# cube8.net
KiCad netlist of a schematic drawn in Altium Designer
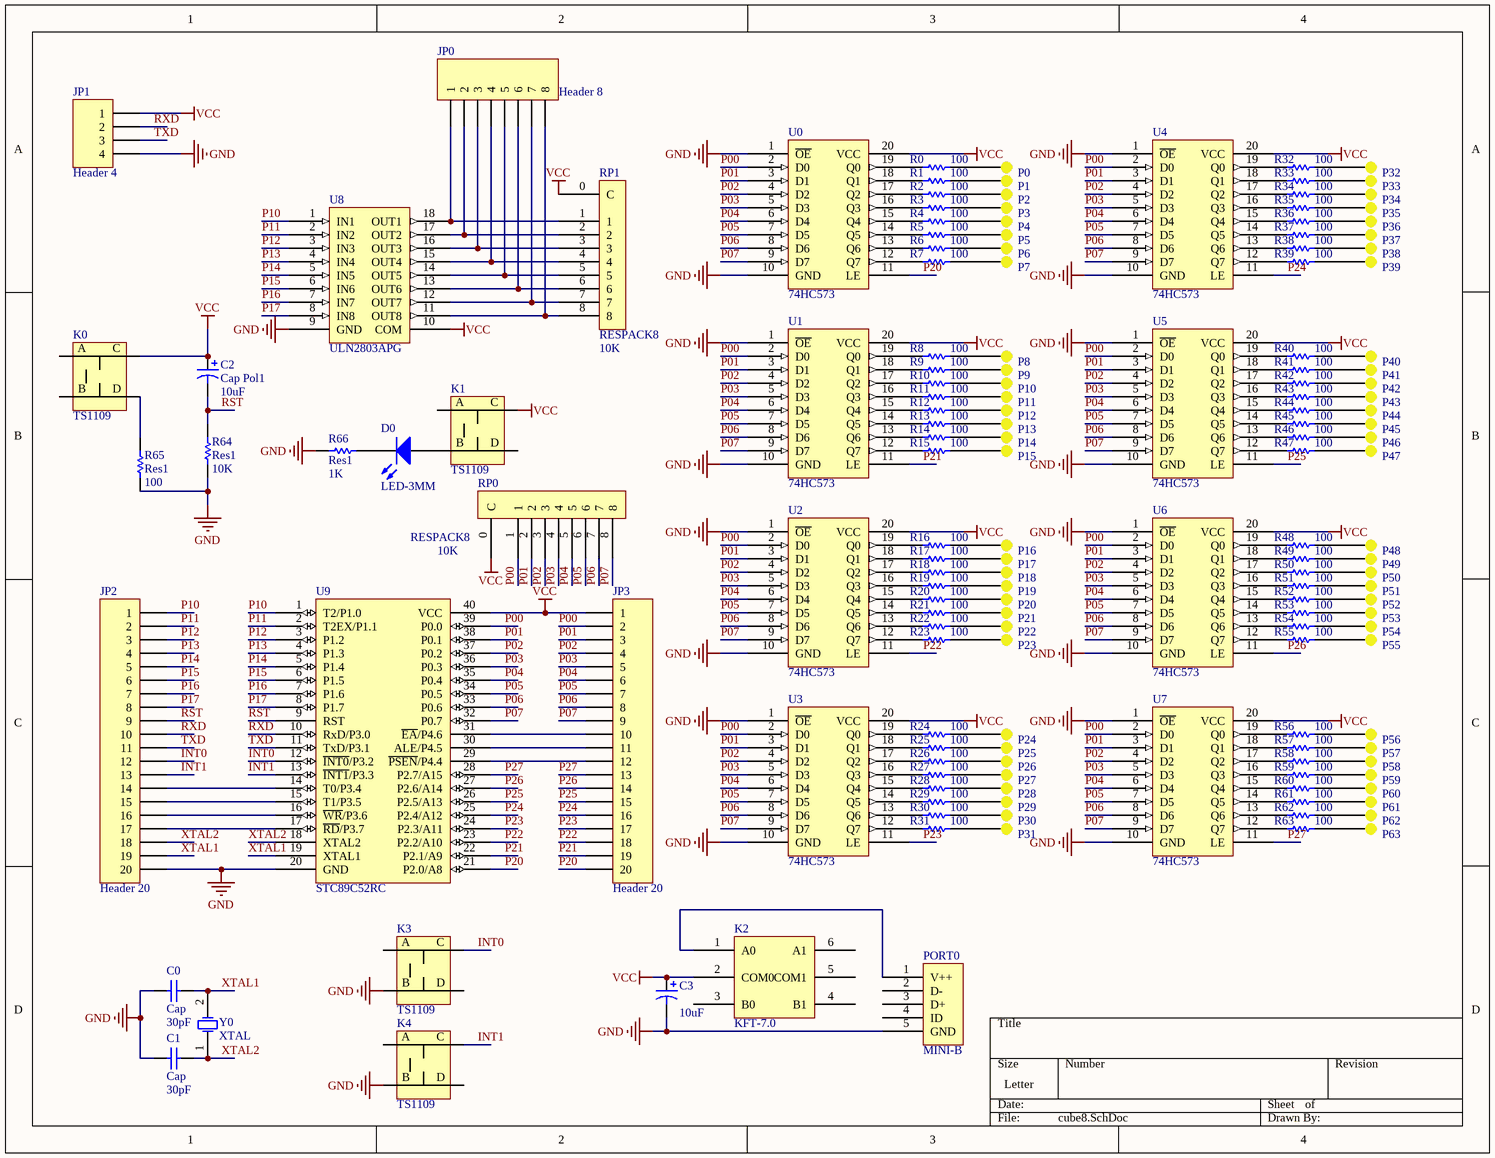
[diagram p0: cube8.SchDoc]

(export (version "E")
  (design (tool "Eeschema 10.0.6"))
  (components
    (comp (ref "C0")
      (value "Cap")
      (footprint "RAD-0.1")
      (description "Capacitor")
      (fields (field (name "ALTIUM_VALUE") "30pF") (field (name "PUBLISHER") "Altium Limited"))
      (libsource (lib "Miscellaneous Devices") (part "Cap"))
    )
    (comp (ref "C1")
      (value "Cap")
      (footprint "RAD-0.1")
      (description "Capacitor")
      (fields (field (name "ALTIUM_VALUE") "30pF") (field (name "PUBLISHER") "Altium Limited"))
      (libsource (lib "Miscellaneous Devices") (part "Cap"))
    )
    (comp (ref "C2")
      (value "Cap Pol1")
      (footprint "RB.1")
      (description "Polarized Capacitor (Radial)")
      (fields (field (name "ALTIUM_VALUE") "10uF") (field (name "PUBLISHER") "Altium Limited"))
      (libsource (lib "Miscellaneous Devices") (part "Cap Pol1"))
    )
    (comp (ref "C3")
      (value "10uF")
      (footprint "RB.1")
      (description "Polarized Capacitor (Radial)")
      (fields (field (name "Comment") "Cap Pol1") (field (name "PUBLISHER") "Altium Limited"))
      (libsource (lib "Miscellaneous Devices") (part "Cap Pol1"))
    )
    (comp (ref "D0")
      (value "LED-3MM")
      (footprint "LED3")
      (description "Typical INFRARED GaAs LED")
      (fields (field (name "PUBLISHER") "Altium Limited"))
      (libsource (lib "Miscellaneous Devices") (part "LED0"))
    )
    (comp (ref "JP0")
      (value "Header 8")
      (footprint "HDR1X8")
      (description "Header, 8-Pin")
      (fields (field (name "PUBLISHER") "Altium Limited"))
      (libsource (lib "Miscellaneous Connectors") (part "Header 8"))
    )
    (comp (ref "JP1")
      (value "Header 4")
      (footprint "PIN4")
      (description "Header, 4-Pin")
      (fields (field (name "PUBLISHER") "Altium Limited"))
      (libsource (lib "Miscellaneous Connectors") (part "Header 4"))
    )
    (comp (ref "JP2")
      (value "Header 20")
      (footprint "HDR1X20")
      (description "Header, 20-Pin")
      (fields (field (name "PUBLISHER") "Altium Limited"))
      (libsource (lib "") (part "Header 20_1"))
    )
    (comp (ref "JP3")
      (value "Header 20")
      (footprint "HDR1X20")
      (description "Header, 20-Pin")
      (fields (field (name "PUBLISHER") "Altium Limited"))
      (libsource (lib "Miscellaneous Connectors") (part "Header 20"))
    )
    (comp (ref "K0") (value "TS1109") (footprint "TS-1109") (libsource (lib "cube8") (part "TS-1109")))
    (comp (ref "K1") (value "TS1109") (footprint "TS-1109") (libsource (lib "cube8") (part "TS-1109")))
    (comp (ref "K2") (value "KFT-7.0") (footprint "KFT-7.0") (libsource (lib "cube8") (part "KFT-7.0")))
    (comp (ref "K3") (value "TS1109") (footprint "TS-1109") (libsource (lib "cube8") (part "TS-1109")))
    (comp (ref "K4") (value "TS1109") (footprint "TS-1109") (libsource (lib "cube8") (part "TS-1109")))
    (comp (ref "P0") (value "PIN") (footprint "PIN1") (libsource (lib "cube8") (part "PIN1")))
    (comp (ref "P1") (value "PIN") (footprint "PIN1") (libsource (lib "cube8") (part "PIN1")))
    (comp (ref "P2") (value "PIN") (footprint "PIN1") (libsource (lib "cube8") (part "PIN1")))
    (comp (ref "P3") (value "PIN") (footprint "PIN1") (libsource (lib "cube8") (part "PIN1")))
    (comp (ref "P4") (value "PIN") (footprint "PIN1") (libsource (lib "cube8") (part "PIN1")))
    (comp (ref "P5") (value "PIN") (footprint "PIN1") (libsource (lib "cube8") (part "PIN1")))
    (comp (ref "P6") (value "PIN") (footprint "PIN1") (libsource (lib "cube8") (part "PIN1")))
    (comp (ref "P7") (value "PIN") (footprint "PIN1") (libsource (lib "cube8") (part "PIN1")))
    (comp (ref "P8") (value "PIN") (footprint "PIN1") (libsource (lib "cube8") (part "PIN1")))
    (comp (ref "P9") (value "PIN") (footprint "PIN1") (libsource (lib "cube8") (part "PIN1")))
    (comp (ref "P10") (value "PIN") (footprint "PIN1") (libsource (lib "cube8") (part "PIN1")))
    (comp (ref "P11") (value "PIN") (footprint "PIN1") (libsource (lib "cube8") (part "PIN1")))
    (comp (ref "P12") (value "PIN") (footprint "PIN1") (libsource (lib "cube8") (part "PIN1")))
    (comp (ref "P13") (value "PIN") (footprint "PIN1") (libsource (lib "cube8") (part "PIN1")))
    (comp (ref "P14") (value "PIN") (footprint "PIN1") (libsource (lib "cube8") (part "PIN1")))
    (comp (ref "P15") (value "PIN") (footprint "PIN1") (libsource (lib "cube8") (part "PIN1")))
    (comp (ref "P16") (value "PIN") (footprint "PIN1") (libsource (lib "cube8") (part "PIN1")))
    (comp (ref "P17") (value "PIN") (footprint "PIN1") (libsource (lib "cube8") (part "PIN1")))
    (comp (ref "P18") (value "PIN") (footprint "PIN1") (libsource (lib "cube8") (part "PIN1")))
    (comp (ref "P19") (value "PIN") (footprint "PIN1") (libsource (lib "cube8") (part "PIN1")))
    (comp (ref "P20") (value "PIN") (footprint "PIN1") (libsource (lib "cube8") (part "PIN1")))
    (comp (ref "P21") (value "PIN") (footprint "PIN1") (libsource (lib "cube8") (part "PIN1")))
    (comp (ref "P22") (value "PIN") (footprint "PIN1") (libsource (lib "cube8") (part "PIN1")))
    (comp (ref "P23") (value "PIN") (footprint "PIN1") (libsource (lib "cube8") (part "PIN1")))
    (comp (ref "P24") (value "PIN") (footprint "PIN1") (libsource (lib "cube8") (part "PIN1")))
    (comp (ref "P25") (value "PIN") (footprint "PIN1") (libsource (lib "cube8") (part "PIN1")))
    (comp (ref "P26") (value "PIN") (footprint "PIN1") (libsource (lib "cube8") (part "PIN1")))
    (comp (ref "P27") (value "PIN") (footprint "PIN1") (libsource (lib "cube8") (part "PIN1")))
    (comp (ref "P28") (value "PIN") (footprint "PIN1") (libsource (lib "cube8") (part "PIN1")))
    (comp (ref "P29") (value "PIN") (footprint "PIN1") (libsource (lib "cube8") (part "PIN1")))
    (comp (ref "P30") (value "PIN") (footprint "PIN1") (libsource (lib "cube8") (part "PIN1")))
    (comp (ref "P31") (value "PIN") (footprint "PIN1") (libsource (lib "cube8") (part "PIN1")))
    (comp (ref "P32") (value "PIN") (footprint "PIN1") (libsource (lib "cube8") (part "PIN1")))
    (comp (ref "P33") (value "PIN") (footprint "PIN1") (libsource (lib "cube8") (part "PIN1")))
    (comp (ref "P34") (value "PIN") (footprint "PIN1") (libsource (lib "cube8") (part "PIN1")))
    (comp (ref "P35") (value "PIN") (footprint "PIN1") (libsource (lib "cube8") (part "PIN1")))
    (comp (ref "P36") (value "PIN") (footprint "PIN1") (libsource (lib "cube8") (part "PIN1")))
    (comp (ref "P37") (value "PIN") (footprint "PIN1") (libsource (lib "cube8") (part "PIN1")))
    (comp (ref "P38") (value "PIN") (footprint "PIN1") (libsource (lib "cube8") (part "PIN1")))
    (comp (ref "P39") (value "PIN") (footprint "PIN1") (libsource (lib "cube8") (part "PIN1")))
    (comp (ref "P40") (value "PIN") (footprint "PIN1") (libsource (lib "cube8") (part "PIN1")))
    (comp (ref "P41") (value "PIN") (footprint "PIN1") (libsource (lib "cube8") (part "PIN1")))
    (comp (ref "P42") (value "PIN") (footprint "PIN1") (libsource (lib "cube8") (part "PIN1")))
    (comp (ref "P43") (value "PIN") (footprint "PIN1") (libsource (lib "cube8") (part "PIN1")))
    (comp (ref "P44") (value "PIN") (footprint "PIN1") (libsource (lib "cube8") (part "PIN1")))
    (comp (ref "P45") (value "PIN") (footprint "PIN1") (libsource (lib "cube8") (part "PIN1")))
    (comp (ref "P46") (value "PIN") (footprint "PIN1") (libsource (lib "cube8") (part "PIN1")))
    (comp (ref "P47") (value "PIN") (footprint "PIN1") (libsource (lib "cube8") (part "PIN1")))
    (comp (ref "P48") (value "PIN") (footprint "PIN1") (libsource (lib "cube8") (part "PIN1")))
    (comp (ref "P49") (value "PIN") (footprint "PIN1") (libsource (lib "cube8") (part "PIN1")))
    (comp (ref "P50") (value "PIN") (footprint "PIN1") (libsource (lib "cube8") (part "PIN1")))
    (comp (ref "P51") (value "PIN") (footprint "PIN1") (libsource (lib "cube8") (part "PIN1")))
    (comp (ref "P52") (value "PIN") (footprint "PIN1") (libsource (lib "cube8") (part "PIN1")))
    (comp (ref "P53") (value "PIN") (footprint "PIN1") (libsource (lib "cube8") (part "PIN1")))
    (comp (ref "P54") (value "PIN") (footprint "PIN1") (libsource (lib "cube8") (part "PIN1")))
    (comp (ref "P55") (value "PIN") (footprint "PIN1") (libsource (lib "cube8") (part "PIN1")))
    (comp (ref "P56") (value "PIN") (footprint "PIN1") (libsource (lib "cube8") (part "PIN1")))
    (comp (ref "P57") (value "PIN") (footprint "PIN1") (libsource (lib "cube8") (part "PIN1")))
    (comp (ref "P58") (value "PIN") (footprint "PIN1") (libsource (lib "cube8") (part "PIN1")))
    (comp (ref "P59") (value "PIN") (footprint "PIN1") (libsource (lib "cube8") (part "PIN1")))
    (comp (ref "P60") (value "PIN") (footprint "PIN1") (libsource (lib "cube8") (part "PIN1")))
    (comp (ref "P61") (value "PIN") (footprint "PIN1") (libsource (lib "cube8") (part "PIN1")))
    (comp (ref "P62") (value "PIN") (footprint "PIN1") (libsource (lib "cube8") (part "PIN1")))
    (comp (ref "P63") (value "PIN") (footprint "PIN1") (libsource (lib "cube8") (part "PIN1")))
    (comp (ref "PORT0") (value "MINI-B") (footprint "MINI-B") (libsource (lib "cube8") (part "MINI-B")))
    (comp (ref "R0")
      (value "100")
      (footprint "AXIAL-0.3")
      (description "Resistor")
      (fields (field (name "Comment") "Res1") (field (name "PUBLISHER") "Altium Limited"))
      (libsource (lib "Miscellaneous Devices") (part "Res1"))
    )
    (comp (ref "R1")
      (value "100")
      (footprint "AXIAL-0.3")
      (description "Resistor")
      (fields (field (name "Comment") "Res1") (field (name "PUBLISHER") "Altium Limited"))
      (libsource (lib "Miscellaneous Devices") (part "Res1"))
    )
    (comp (ref "R2")
      (value "100")
      (footprint "AXIAL-0.3")
      (description "Resistor")
      (fields (field (name "Comment") "Res1") (field (name "PUBLISHER") "Altium Limited"))
      (libsource (lib "Miscellaneous Devices") (part "Res1"))
    )
    (comp (ref "R3")
      (value "100")
      (footprint "AXIAL-0.3")
      (description "Resistor")
      (fields (field (name "Comment") "Res1") (field (name "PUBLISHER") "Altium Limited"))
      (libsource (lib "Miscellaneous Devices") (part "Res1"))
    )
    (comp (ref "R4")
      (value "100")
      (footprint "AXIAL-0.3")
      (description "Resistor")
      (fields (field (name "Comment") "Res1") (field (name "PUBLISHER") "Altium Limited"))
      (libsource (lib "Miscellaneous Devices") (part "Res1"))
    )
    (comp (ref "R5")
      (value "100")
      (footprint "AXIAL-0.3")
      (description "Resistor")
      (fields (field (name "Comment") "Res1") (field (name "PUBLISHER") "Altium Limited"))
      (libsource (lib "Miscellaneous Devices") (part "Res1"))
    )
    (comp (ref "R6")
      (value "100")
      (footprint "AXIAL-0.3")
      (description "Resistor")
      (fields (field (name "Comment") "Res1") (field (name "PUBLISHER") "Altium Limited"))
      (libsource (lib "Miscellaneous Devices") (part "Res1"))
    )
    (comp (ref "R7")
      (value "100")
      (footprint "AXIAL-0.3")
      (description "Resistor")
      (fields (field (name "Comment") "Res1") (field (name "PUBLISHER") "Altium Limited"))
      (libsource (lib "Miscellaneous Devices") (part "Res1"))
    )
    (comp (ref "R8")
      (value "100")
      (footprint "AXIAL-0.3")
      (description "Resistor")
      (fields (field (name "Comment") "Res1") (field (name "PUBLISHER") "Altium Limited"))
      (libsource (lib "Miscellaneous Devices") (part "Res1"))
    )
    (comp (ref "R9")
      (value "100")
      (footprint "AXIAL-0.3")
      (description "Resistor")
      (fields (field (name "Comment") "Res1") (field (name "PUBLISHER") "Altium Limited"))
      (libsource (lib "Miscellaneous Devices") (part "Res1"))
    )
    (comp (ref "R10")
      (value "100")
      (footprint "AXIAL-0.3")
      (description "Resistor")
      (fields (field (name "Comment") "Res1") (field (name "PUBLISHER") "Altium Limited"))
      (libsource (lib "Miscellaneous Devices") (part "Res1"))
    )
    (comp (ref "R11")
      (value "100")
      (footprint "AXIAL-0.3")
      (description "Resistor")
      (fields (field (name "Comment") "Res1") (field (name "PUBLISHER") "Altium Limited"))
      (libsource (lib "Miscellaneous Devices") (part "Res1"))
    )
    (comp (ref "R12")
      (value "100")
      (footprint "AXIAL-0.3")
      (description "Resistor")
      (fields (field (name "Comment") "Res1") (field (name "PUBLISHER") "Altium Limited"))
      (libsource (lib "Miscellaneous Devices") (part "Res1"))
    )
    (comp (ref "R13")
      (value "100")
      (footprint "AXIAL-0.3")
      (description "Resistor")
      (fields (field (name "Comment") "Res1") (field (name "PUBLISHER") "Altium Limited"))
      (libsource (lib "Miscellaneous Devices") (part "Res1"))
    )
    (comp (ref "R14")
      (value "100")
      (footprint "AXIAL-0.3")
      (description "Resistor")
      (fields (field (name "Comment") "Res1") (field (name "PUBLISHER") "Altium Limited"))
      (libsource (lib "Miscellaneous Devices") (part "Res1"))
    )
    (comp (ref "R15")
      (value "100")
      (footprint "AXIAL-0.3")
      (description "Resistor")
      (fields (field (name "Comment") "Res1") (field (name "PUBLISHER") "Altium Limited"))
      (libsource (lib "Miscellaneous Devices") (part "Res1"))
    )
    (comp (ref "R16")
      (value "100")
      (footprint "AXIAL-0.3")
      (description "Resistor")
      (fields (field (name "Comment") "Res1") (field (name "PUBLISHER") "Altium Limited"))
      (libsource (lib "Miscellaneous Devices") (part "Res1"))
    )
    (comp (ref "R17")
      (value "100")
      (footprint "AXIAL-0.3")
      (description "Resistor")
      (fields (field (name "Comment") "Res1") (field (name "PUBLISHER") "Altium Limited"))
      (libsource (lib "Miscellaneous Devices") (part "Res1"))
    )
    (comp (ref "R18")
      (value "100")
      (footprint "AXIAL-0.3")
      (description "Resistor")
      (fields (field (name "Comment") "Res1") (field (name "PUBLISHER") "Altium Limited"))
      (libsource (lib "Miscellaneous Devices") (part "Res1"))
    )
    (comp (ref "R19")
      (value "100")
      (footprint "AXIAL-0.3")
      (description "Resistor")
      (fields (field (name "Comment") "Res1") (field (name "PUBLISHER") "Altium Limited"))
      (libsource (lib "Miscellaneous Devices") (part "Res1"))
    )
    (comp (ref "R20")
      (value "100")
      (footprint "AXIAL-0.3")
      (description "Resistor")
      (fields (field (name "Comment") "Res1") (field (name "PUBLISHER") "Altium Limited"))
      (libsource (lib "Miscellaneous Devices") (part "Res1"))
    )
    (comp (ref "R21")
      (value "100")
      (footprint "AXIAL-0.3")
      (description "Resistor")
      (fields (field (name "Comment") "Res1") (field (name "PUBLISHER") "Altium Limited"))
      (libsource (lib "Miscellaneous Devices") (part "Res1"))
    )
    (comp (ref "R22")
      (value "100")
      (footprint "AXIAL-0.3")
      (description "Resistor")
      (fields (field (name "Comment") "Res1") (field (name "PUBLISHER") "Altium Limited"))
      (libsource (lib "Miscellaneous Devices") (part "Res1"))
    )
    (comp (ref "R23")
      (value "100")
      (footprint "AXIAL-0.3")
      (description "Resistor")
      (fields (field (name "Comment") "Res1") (field (name "PUBLISHER") "Altium Limited"))
      (libsource (lib "Miscellaneous Devices") (part "Res1"))
    )
    (comp (ref "R24")
      (value "100")
      (footprint "AXIAL-0.3")
      (description "Resistor")
      (fields (field (name "Comment") "Res1") (field (name "PUBLISHER") "Altium Limited"))
      (libsource (lib "Miscellaneous Devices") (part "Res1"))
    )
    (comp (ref "R25")
      (value "100")
      (footprint "AXIAL-0.3")
      (description "Resistor")
      (fields (field (name "Comment") "Res1") (field (name "PUBLISHER") "Altium Limited"))
      (libsource (lib "Miscellaneous Devices") (part "Res1"))
    )
    (comp (ref "R26")
      (value "100")
      (footprint "AXIAL-0.3")
      (description "Resistor")
      (fields (field (name "Comment") "Res1") (field (name "PUBLISHER") "Altium Limited"))
      (libsource (lib "Miscellaneous Devices") (part "Res1"))
    )
    (comp (ref "R27")
      (value "100")
      (footprint "AXIAL-0.3")
      (description "Resistor")
      (fields (field (name "Comment") "Res1") (field (name "PUBLISHER") "Altium Limited"))
      (libsource (lib "Miscellaneous Devices") (part "Res1"))
    )
    (comp (ref "R28")
      (value "100")
      (footprint "AXIAL-0.3")
      (description "Resistor")
      (fields (field (name "Comment") "Res1") (field (name "PUBLISHER") "Altium Limited"))
      (libsource (lib "Miscellaneous Devices") (part "Res1"))
    )
    (comp (ref "R29")
      (value "100")
      (footprint "AXIAL-0.3")
      (description "Resistor")
      (fields (field (name "Comment") "Res1") (field (name "PUBLISHER") "Altium Limited"))
      (libsource (lib "Miscellaneous Devices") (part "Res1"))
    )
    (comp (ref "R30")
      (value "100")
      (footprint "AXIAL-0.3")
      (description "Resistor")
      (fields (field (name "Comment") "Res1") (field (name "PUBLISHER") "Altium Limited"))
      (libsource (lib "Miscellaneous Devices") (part "Res1"))
    )
    (comp (ref "R31")
      (value "100")
      (footprint "AXIAL-0.3")
      (description "Resistor")
      (fields (field (name "Comment") "Res1") (field (name "PUBLISHER") "Altium Limited"))
      (libsource (lib "Miscellaneous Devices") (part "Res1"))
    )
    (comp (ref "R32")
      (value "100")
      (footprint "AXIAL-0.3")
      (description "Resistor")
      (fields (field (name "Comment") "Res1") (field (name "PUBLISHER") "Altium Limited"))
      (libsource (lib "Miscellaneous Devices") (part "Res1"))
    )
    (comp (ref "R33")
      (value "100")
      (footprint "AXIAL-0.3")
      (description "Resistor")
      (fields (field (name "Comment") "Res1") (field (name "PUBLISHER") "Altium Limited"))
      (libsource (lib "Miscellaneous Devices") (part "Res1"))
    )
    (comp (ref "R34")
      (value "100")
      (footprint "AXIAL-0.3")
      (description "Resistor")
      (fields (field (name "Comment") "Res1") (field (name "PUBLISHER") "Altium Limited"))
      (libsource (lib "Miscellaneous Devices") (part "Res1"))
    )
    (comp (ref "R35")
      (value "100")
      (footprint "AXIAL-0.3")
      (description "Resistor")
      (fields (field (name "Comment") "Res1") (field (name "PUBLISHER") "Altium Limited"))
      (libsource (lib "Miscellaneous Devices") (part "Res1"))
    )
    (comp (ref "R36")
      (value "100")
      (footprint "AXIAL-0.3")
      (description "Resistor")
      (fields (field (name "Comment") "Res1") (field (name "PUBLISHER") "Altium Limited"))
      (libsource (lib "Miscellaneous Devices") (part "Res1"))
    )
    (comp (ref "R37")
      (value "100")
      (footprint "AXIAL-0.3")
      (description "Resistor")
      (fields (field (name "Comment") "Res1") (field (name "PUBLISHER") "Altium Limited"))
      (libsource (lib "Miscellaneous Devices") (part "Res1"))
    )
    (comp (ref "R38")
      (value "100")
      (footprint "AXIAL-0.3")
      (description "Resistor")
      (fields (field (name "Comment") "Res1") (field (name "PUBLISHER") "Altium Limited"))
      (libsource (lib "Miscellaneous Devices") (part "Res1"))
    )
    (comp (ref "R39")
      (value "100")
      (footprint "AXIAL-0.3")
      (description "Resistor")
      (fields (field (name "Comment") "Res1") (field (name "PUBLISHER") "Altium Limited"))
      (libsource (lib "Miscellaneous Devices") (part "Res1"))
    )
    (comp (ref "R40")
      (value "100")
      (footprint "AXIAL-0.3")
      (description "Resistor")
      (fields (field (name "Comment") "Res1") (field (name "PUBLISHER") "Altium Limited"))
      (libsource (lib "Miscellaneous Devices") (part "Res1"))
    )
    (comp (ref "R41")
      (value "100")
      (footprint "AXIAL-0.3")
      (description "Resistor")
      (fields (field (name "Comment") "Res1") (field (name "PUBLISHER") "Altium Limited"))
      (libsource (lib "Miscellaneous Devices") (part "Res1"))
    )
    (comp (ref "R42")
      (value "100")
      (footprint "AXIAL-0.3")
      (description "Resistor")
      (fields (field (name "Comment") "Res1") (field (name "PUBLISHER") "Altium Limited"))
      (libsource (lib "Miscellaneous Devices") (part "Res1"))
    )
    (comp (ref "R43")
      (value "100")
      (footprint "AXIAL-0.3")
      (description "Resistor")
      (fields (field (name "Comment") "Res1") (field (name "PUBLISHER") "Altium Limited"))
      (libsource (lib "Miscellaneous Devices") (part "Res1"))
    )
    (comp (ref "R44")
      (value "100")
      (footprint "AXIAL-0.3")
      (description "Resistor")
      (fields (field (name "Comment") "Res1") (field (name "PUBLISHER") "Altium Limited"))
      (libsource (lib "Miscellaneous Devices") (part "Res1"))
    )
    (comp (ref "R45")
      (value "100")
      (footprint "AXIAL-0.3")
      (description "Resistor")
      (fields (field (name "Comment") "Res1") (field (name "PUBLISHER") "Altium Limited"))
      (libsource (lib "Miscellaneous Devices") (part "Res1"))
    )
    (comp (ref "R46")
      (value "100")
      (footprint "AXIAL-0.3")
      (description "Resistor")
      (fields (field (name "Comment") "Res1") (field (name "PUBLISHER") "Altium Limited"))
      (libsource (lib "Miscellaneous Devices") (part "Res1"))
    )
    (comp (ref "R47")
      (value "100")
      (footprint "AXIAL-0.3")
      (description "Resistor")
      (fields (field (name "Comment") "Res1") (field (name "PUBLISHER") "Altium Limited"))
      (libsource (lib "Miscellaneous Devices") (part "Res1"))
    )
    (comp (ref "R48")
      (value "100")
      (footprint "AXIAL-0.3")
      (description "Resistor")
      (fields (field (name "Comment") "Res1") (field (name "PUBLISHER") "Altium Limited"))
      (libsource (lib "Miscellaneous Devices") (part "Res1"))
    )
    (comp (ref "R49")
      (value "100")
      (footprint "AXIAL-0.3")
      (description "Resistor")
      (fields (field (name "Comment") "Res1") (field (name "PUBLISHER") "Altium Limited"))
      (libsource (lib "Miscellaneous Devices") (part "Res1"))
    )
    (comp (ref "R50")
      (value "100")
      (footprint "AXIAL-0.3")
      (description "Resistor")
      (fields (field (name "Comment") "Res1") (field (name "PUBLISHER") "Altium Limited"))
      (libsource (lib "Miscellaneous Devices") (part "Res1"))
    )
    (comp (ref "R51")
      (value "100")
      (footprint "AXIAL-0.3")
      (description "Resistor")
      (fields (field (name "Comment") "Res1") (field (name "PUBLISHER") "Altium Limited"))
      (libsource (lib "Miscellaneous Devices") (part "Res1"))
    )
    (comp (ref "R52")
      (value "100")
      (footprint "AXIAL-0.3")
      (description "Resistor")
      (fields (field (name "Comment") "Res1") (field (name "PUBLISHER") "Altium Limited"))
      (libsource (lib "Miscellaneous Devices") (part "Res1"))
    )
    (comp (ref "R53")
      (value "100")
      (footprint "AXIAL-0.3")
      (description "Resistor")
      (fields (field (name "Comment") "Res1") (field (name "PUBLISHER") "Altium Limited"))
      (libsource (lib "Miscellaneous Devices") (part "Res1"))
    )
    (comp (ref "R54")
      (value "100")
      (footprint "AXIAL-0.3")
      (description "Resistor")
      (fields (field (name "Comment") "Res1") (field (name "PUBLISHER") "Altium Limited"))
      (libsource (lib "Miscellaneous Devices") (part "Res1"))
    )
    (comp (ref "R55")
      (value "100")
      (footprint "AXIAL-0.3")
      (description "Resistor")
      (fields (field (name "Comment") "Res1") (field (name "PUBLISHER") "Altium Limited"))
      (libsource (lib "Miscellaneous Devices") (part "Res1"))
    )
    (comp (ref "R56")
      (value "100")
      (footprint "AXIAL-0.3")
      (description "Resistor")
      (fields (field (name "Comment") "Res1") (field (name "PUBLISHER") "Altium Limited"))
      (libsource (lib "Miscellaneous Devices") (part "Res1"))
    )
    (comp (ref "R57")
      (value "100")
      (footprint "AXIAL-0.3")
      (description "Resistor")
      (fields (field (name "Comment") "Res1") (field (name "PUBLISHER") "Altium Limited"))
      (libsource (lib "Miscellaneous Devices") (part "Res1"))
    )
    (comp (ref "R58")
      (value "100")
      (footprint "AXIAL-0.3")
      (description "Resistor")
      (fields (field (name "Comment") "Res1") (field (name "PUBLISHER") "Altium Limited"))
      (libsource (lib "Miscellaneous Devices") (part "Res1"))
    )
    (comp (ref "R59")
      (value "100")
      (footprint "AXIAL-0.3")
      (description "Resistor")
      (fields (field (name "Comment") "Res1") (field (name "PUBLISHER") "Altium Limited"))
      (libsource (lib "Miscellaneous Devices") (part "Res1"))
    )
    (comp (ref "R60")
      (value "100")
      (footprint "AXIAL-0.3")
      (description "Resistor")
      (fields (field (name "Comment") "Res1") (field (name "PUBLISHER") "Altium Limited"))
      (libsource (lib "Miscellaneous Devices") (part "Res1"))
    )
    (comp (ref "R61")
      (value "100")
      (footprint "AXIAL-0.3")
      (description "Resistor")
      (fields (field (name "Comment") "Res1") (field (name "PUBLISHER") "Altium Limited"))
      (libsource (lib "Miscellaneous Devices") (part "Res1"))
    )
    (comp (ref "R62")
      (value "100")
      (footprint "AXIAL-0.3")
      (description "Resistor")
      (fields (field (name "Comment") "Res1") (field (name "PUBLISHER") "Altium Limited"))
      (libsource (lib "Miscellaneous Devices") (part "Res1"))
    )
    (comp (ref "R63")
      (value "100")
      (footprint "AXIAL-0.3")
      (description "Resistor")
      (fields (field (name "Comment") "Res1") (field (name "PUBLISHER") "Altium Limited"))
      (libsource (lib "Miscellaneous Devices") (part "Res1"))
    )
    (comp (ref "R64")
      (value "Res1")
      (footprint "AXIAL-0.3")
      (description "Resistor")
      (fields (field (name "ALTIUM_VALUE") "10K") (field (name "PUBLISHER") "Altium Limited"))
      (libsource (lib "Miscellaneous Devices") (part "Res1"))
    )
    (comp (ref "R65")
      (value "Res1")
      (footprint "AXIAL-0.3")
      (description "Resistor")
      (fields (field (name "ALTIUM_VALUE") "100") (field (name "PUBLISHER") "Altium Limited"))
      (libsource (lib "Miscellaneous Devices") (part "Res1"))
    )
    (comp (ref "R66")
      (value "Res1")
      (footprint "AXIAL-0.3")
      (description "Resistor")
      (fields (field (name "ALTIUM_VALUE") "1K") (field (name "PUBLISHER") "Altium Limited"))
      (libsource (lib "Miscellaneous Devices") (part "Res1"))
    )
    (comp (ref "RP0")
      (value "RESPACK8")
      (footprint "SIP9")
      (fields (field (name "ALTIUM_VALUE") "10K"))
      (libsource (lib "cube8") (part "RESPACK8"))
    )
    (comp (ref "RP1")
      (value "RESPACK8")
      (footprint "SIP9")
      (fields (field (name "ALTIUM_VALUE") "10K"))
      (libsource (lib "") (part "RESPACK8_1"))
    )
    (comp (ref "U0") (value "74HC573") (footprint "DIP20") (libsource (lib "cube8") (part "74HC573")))
    (comp (ref "U1") (value "74HC573") (footprint "DIP20") (libsource (lib "cube8") (part "74HC573")))
    (comp (ref "U2") (value "74HC573") (footprint "DIP20") (libsource (lib "cube8") (part "74HC573")))
    (comp (ref "U3") (value "74HC573") (footprint "DIP20") (libsource (lib "cube8") (part "74HC573")))
    (comp (ref "U4") (value "74HC573") (footprint "DIP20") (libsource (lib "cube8") (part "74HC573")))
    (comp (ref "U5") (value "74HC573") (footprint "DIP20") (libsource (lib "cube8") (part "74HC573")))
    (comp (ref "U6") (value "74HC573") (footprint "DIP20") (libsource (lib "cube8") (part "74HC573")))
    (comp (ref "U7") (value "74HC573") (footprint "DIP20") (libsource (lib "cube8") (part "74HC573")))
    (comp (ref "U8") (value "ULN2803APG") (footprint "DIP18") (libsource (lib "cube8") (part "ULN2803APG")))
    (comp (ref "U9") (value "STC89C52RC") (footprint "DIP40") (libsource (lib "cube8") (part "STC89C52RC")))
    (comp (ref "Y0")
      (value "XTAL")
      (footprint "HC-49S")
      (description "Crystal Oscillator")
      (fields (field (name "PUBLISHER") "Altium Limited"))
      (libsource (lib "Miscellaneous Devices") (part "XTAL"))
    )
  )
  (nets
    (net (code "1") (name "/INT0") (class "Default")
      (node (ref "JP2") (pin "12") (pinfunction "12_12") (pintype "passive"))
      (node (ref "K3") (pin "C") (pinfunction "12_C") (pintype "passive"))
      (node (ref "U9") (pin "12") (pinfunction "~{INT0}/P3.2_12") (pintype "bidirectional"))
    )
    (net (code "2") (name "/INT1") (class "Default")
      (node (ref "JP2") (pin "13") (pinfunction "13_13") (pintype "passive"))
      (node (ref "K4") (pin "C") (pinfunction "12_C") (pintype "passive"))
      (node (ref "U9") (pin "13") (pinfunction "~{INT1}/P3.3_13") (pintype "bidirectional"))
    )
    (net (code "3") (name "/P00") (class "Default")
      (node (ref "JP3") (pin "2") (pinfunction "2_2") (pintype "passive"))
      (node (ref "RP0") (pin "1") (pinfunction "1_1") (pintype "passive"))
      (node (ref "U0") (pin "2") (pinfunction "D0_2") (pintype "input"))
      (node (ref "U1") (pin "2") (pinfunction "D0_2") (pintype "input"))
      (node (ref "U2") (pin "2") (pinfunction "D0_2") (pintype "input"))
      (node (ref "U3") (pin "2") (pinfunction "D0_2") (pintype "input"))
      (node (ref "U4") (pin "2") (pinfunction "D0_2") (pintype "input"))
      (node (ref "U5") (pin "2") (pinfunction "D0_2") (pintype "input"))
      (node (ref "U6") (pin "2") (pinfunction "D0_2") (pintype "input"))
      (node (ref "U7") (pin "2") (pinfunction "D0_2") (pintype "input"))
      (node (ref "U9") (pin "39") (pinfunction "P0.0_39") (pintype "bidirectional"))
    )
    (net (code "4") (name "/P01") (class "Default")
      (node (ref "JP3") (pin "3") (pinfunction "3_3") (pintype "passive"))
      (node (ref "RP0") (pin "2") (pinfunction "2_2") (pintype "passive"))
      (node (ref "U0") (pin "3") (pinfunction "D1_3") (pintype "input"))
      (node (ref "U1") (pin "3") (pinfunction "D1_3") (pintype "input"))
      (node (ref "U2") (pin "3") (pinfunction "D1_3") (pintype "input"))
      (node (ref "U3") (pin "3") (pinfunction "D1_3") (pintype "input"))
      (node (ref "U4") (pin "3") (pinfunction "D1_3") (pintype "input"))
      (node (ref "U5") (pin "3") (pinfunction "D1_3") (pintype "input"))
      (node (ref "U6") (pin "3") (pinfunction "D1_3") (pintype "input"))
      (node (ref "U7") (pin "3") (pinfunction "D1_3") (pintype "input"))
      (node (ref "U9") (pin "38") (pinfunction "P0.1_38") (pintype "bidirectional"))
    )
    (net (code "5") (name "/P02") (class "Default")
      (node (ref "JP3") (pin "4") (pinfunction "4_4") (pintype "passive"))
      (node (ref "RP0") (pin "3") (pinfunction "3_3") (pintype "passive"))
      (node (ref "U0") (pin "4") (pinfunction "D2_4") (pintype "input"))
      (node (ref "U1") (pin "4") (pinfunction "D2_4") (pintype "input"))
      (node (ref "U2") (pin "4") (pinfunction "D2_4") (pintype "input"))
      (node (ref "U3") (pin "4") (pinfunction "D2_4") (pintype "input"))
      (node (ref "U4") (pin "4") (pinfunction "D2_4") (pintype "input"))
      (node (ref "U5") (pin "4") (pinfunction "D2_4") (pintype "input"))
      (node (ref "U6") (pin "4") (pinfunction "D2_4") (pintype "input"))
      (node (ref "U7") (pin "4") (pinfunction "D2_4") (pintype "input"))
      (node (ref "U9") (pin "37") (pinfunction "P0.2_37") (pintype "bidirectional"))
    )
    (net (code "6") (name "/P03") (class "Default")
      (node (ref "JP3") (pin "5") (pinfunction "5_5") (pintype "passive"))
      (node (ref "RP0") (pin "4") (pinfunction "4_4") (pintype "passive"))
      (node (ref "U0") (pin "5") (pinfunction "D3_5") (pintype "input"))
      (node (ref "U1") (pin "5") (pinfunction "D3_5") (pintype "input"))
      (node (ref "U2") (pin "5") (pinfunction "D3_5") (pintype "input"))
      (node (ref "U3") (pin "5") (pinfunction "D3_5") (pintype "input"))
      (node (ref "U4") (pin "5") (pinfunction "D3_5") (pintype "input"))
      (node (ref "U5") (pin "5") (pinfunction "D3_5") (pintype "input"))
      (node (ref "U6") (pin "5") (pinfunction "D3_5") (pintype "input"))
      (node (ref "U7") (pin "5") (pinfunction "D3_5") (pintype "input"))
      (node (ref "U9") (pin "36") (pinfunction "P0.3_36") (pintype "bidirectional"))
    )
    (net (code "7") (name "/P04") (class "Default")
      (node (ref "JP3") (pin "6") (pinfunction "6_6") (pintype "passive"))
      (node (ref "RP0") (pin "5") (pinfunction "5_5") (pintype "passive"))
      (node (ref "U0") (pin "6") (pinfunction "D4_6") (pintype "input"))
      (node (ref "U1") (pin "6") (pinfunction "D4_6") (pintype "input"))
      (node (ref "U2") (pin "6") (pinfunction "D4_6") (pintype "input"))
      (node (ref "U3") (pin "6") (pinfunction "D4_6") (pintype "input"))
      (node (ref "U4") (pin "6") (pinfunction "D4_6") (pintype "input"))
      (node (ref "U5") (pin "6") (pinfunction "D4_6") (pintype "input"))
      (node (ref "U6") (pin "6") (pinfunction "D4_6") (pintype "input"))
      (node (ref "U7") (pin "6") (pinfunction "D4_6") (pintype "input"))
      (node (ref "U9") (pin "35") (pinfunction "P0.4_35") (pintype "bidirectional"))
    )
    (net (code "8") (name "/P05") (class "Default")
      (node (ref "JP3") (pin "7") (pinfunction "7_7") (pintype "passive"))
      (node (ref "RP0") (pin "6") (pinfunction "6_6") (pintype "passive"))
      (node (ref "U0") (pin "7") (pinfunction "D5_7") (pintype "input"))
      (node (ref "U1") (pin "7") (pinfunction "D5_7") (pintype "input"))
      (node (ref "U2") (pin "7") (pinfunction "D5_7") (pintype "input"))
      (node (ref "U3") (pin "7") (pinfunction "D5_7") (pintype "input"))
      (node (ref "U4") (pin "7") (pinfunction "D5_7") (pintype "input"))
      (node (ref "U5") (pin "7") (pinfunction "D5_7") (pintype "input"))
      (node (ref "U6") (pin "7") (pinfunction "D5_7") (pintype "input"))
      (node (ref "U7") (pin "7") (pinfunction "D5_7") (pintype "input"))
      (node (ref "U9") (pin "34") (pinfunction "P0.5_34") (pintype "bidirectional"))
    )
    (net (code "9") (name "/P06") (class "Default")
      (node (ref "JP3") (pin "8") (pinfunction "8_8") (pintype "passive"))
      (node (ref "RP0") (pin "7") (pinfunction "7_7") (pintype "passive"))
      (node (ref "U0") (pin "8") (pinfunction "D6_8") (pintype "input"))
      (node (ref "U1") (pin "8") (pinfunction "D6_8") (pintype "input"))
      (node (ref "U2") (pin "8") (pinfunction "D6_8") (pintype "input"))
      (node (ref "U3") (pin "8") (pinfunction "D6_8") (pintype "input"))
      (node (ref "U4") (pin "8") (pinfunction "D6_8") (pintype "input"))
      (node (ref "U5") (pin "8") (pinfunction "D6_8") (pintype "input"))
      (node (ref "U6") (pin "8") (pinfunction "D6_8") (pintype "input"))
      (node (ref "U7") (pin "8") (pinfunction "D6_8") (pintype "input"))
      (node (ref "U9") (pin "33") (pinfunction "P0.6_33") (pintype "bidirectional"))
    )
    (net (code "10") (name "/P07") (class "Default")
      (node (ref "JP3") (pin "9") (pinfunction "9_9") (pintype "passive"))
      (node (ref "RP0") (pin "8") (pinfunction "8_8") (pintype "passive"))
      (node (ref "U0") (pin "9") (pinfunction "D7_9") (pintype "input"))
      (node (ref "U1") (pin "9") (pinfunction "D7_9") (pintype "input"))
      (node (ref "U2") (pin "9") (pinfunction "D7_9") (pintype "input"))
      (node (ref "U3") (pin "9") (pinfunction "D7_9") (pintype "input"))
      (node (ref "U4") (pin "9") (pinfunction "D7_9") (pintype "input"))
      (node (ref "U5") (pin "9") (pinfunction "D7_9") (pintype "input"))
      (node (ref "U6") (pin "9") (pinfunction "D7_9") (pintype "input"))
      (node (ref "U7") (pin "9") (pinfunction "D7_9") (pintype "input"))
      (node (ref "U9") (pin "32") (pinfunction "P0.7_32") (pintype "bidirectional"))
    )
    (net (code "11") (name "/P10") (class "Default")
      (node (ref "JP2") (pin "1") (pinfunction "1_1") (pintype "passive"))
      (node (ref "U8") (pin "1") (pinfunction "IN1_1") (pintype "input"))
      (node (ref "U9") (pin "1") (pinfunction "T2/P1.0_1") (pintype "bidirectional"))
    )
    (net (code "12") (name "/P11") (class "Default")
      (node (ref "JP2") (pin "2") (pinfunction "2_2") (pintype "passive"))
      (node (ref "U8") (pin "2") (pinfunction "IN2_2") (pintype "input"))
      (node (ref "U9") (pin "2") (pinfunction "T2EX/P1.1_2") (pintype "bidirectional"))
    )
    (net (code "13") (name "/P12") (class "Default")
      (node (ref "JP2") (pin "3") (pinfunction "3_3") (pintype "passive"))
      (node (ref "U8") (pin "3") (pinfunction "IN3_3") (pintype "input"))
      (node (ref "U9") (pin "3") (pinfunction "P1.2_3") (pintype "bidirectional"))
    )
    (net (code "14") (name "/P13") (class "Default")
      (node (ref "JP2") (pin "4") (pinfunction "4_4") (pintype "passive"))
      (node (ref "U8") (pin "4") (pinfunction "IN4_4") (pintype "input"))
      (node (ref "U9") (pin "4") (pinfunction "P1.3_4") (pintype "bidirectional"))
    )
    (net (code "15") (name "/P14") (class "Default")
      (node (ref "JP2") (pin "5") (pinfunction "5_5") (pintype "passive"))
      (node (ref "U8") (pin "5") (pinfunction "IN5_5") (pintype "input"))
      (node (ref "U9") (pin "5") (pinfunction "P1.4_5") (pintype "bidirectional"))
    )
    (net (code "16") (name "/P15") (class "Default")
      (node (ref "JP2") (pin "6") (pinfunction "6_6") (pintype "passive"))
      (node (ref "U8") (pin "6") (pinfunction "IN6_6") (pintype "input"))
      (node (ref "U9") (pin "6") (pinfunction "P1.5_6") (pintype "bidirectional"))
    )
    (net (code "17") (name "/P16") (class "Default")
      (node (ref "JP2") (pin "7") (pinfunction "7_7") (pintype "passive"))
      (node (ref "U8") (pin "7") (pinfunction "IN7_7") (pintype "input"))
      (node (ref "U9") (pin "7") (pinfunction "P1.6_7") (pintype "bidirectional"))
    )
    (net (code "18") (name "/P17") (class "Default")
      (node (ref "JP2") (pin "8") (pinfunction "8_8") (pintype "passive"))
      (node (ref "U8") (pin "8") (pinfunction "IN8_8") (pintype "input"))
      (node (ref "U9") (pin "8") (pinfunction "P1.7_8") (pintype "bidirectional"))
    )
    (net (code "19") (name "/P20") (class "Default")
      (node (ref "JP3") (pin "20") (pinfunction "20_20") (pintype "passive"))
      (node (ref "U0") (pin "11") (pinfunction "LE_11") (pintype "passive"))
      (node (ref "U9") (pin "21") (pinfunction "P2.0/A8_21") (pintype "bidirectional"))
    )
    (net (code "20") (name "/P21") (class "Default")
      (node (ref "JP3") (pin "19") (pinfunction "19_19") (pintype "passive"))
      (node (ref "U1") (pin "11") (pinfunction "LE_11") (pintype "passive"))
      (node (ref "U9") (pin "22") (pinfunction "P2.1/A9_22") (pintype "bidirectional"))
    )
    (net (code "21") (name "/P22") (class "Default")
      (node (ref "JP3") (pin "18") (pinfunction "18_18") (pintype "passive"))
      (node (ref "U2") (pin "11") (pinfunction "LE_11") (pintype "passive"))
      (node (ref "U9") (pin "23") (pinfunction "P2.2/A10_23") (pintype "bidirectional"))
    )
    (net (code "22") (name "/P23") (class "Default")
      (node (ref "JP3") (pin "17") (pinfunction "17_17") (pintype "passive"))
      (node (ref "U3") (pin "11") (pinfunction "LE_11") (pintype "passive"))
      (node (ref "U9") (pin "24") (pinfunction "P2.3/A11_24") (pintype "bidirectional"))
    )
    (net (code "23") (name "/P24") (class "Default")
      (node (ref "JP3") (pin "16") (pinfunction "16_16") (pintype "passive"))
      (node (ref "U4") (pin "11") (pinfunction "LE_11") (pintype "passive"))
      (node (ref "U9") (pin "25") (pinfunction "P2.4/A12_25") (pintype "bidirectional"))
    )
    (net (code "24") (name "/P25") (class "Default")
      (node (ref "JP3") (pin "15") (pinfunction "15_15") (pintype "passive"))
      (node (ref "U5") (pin "11") (pinfunction "LE_11") (pintype "passive"))
      (node (ref "U9") (pin "26") (pinfunction "P2.5/A13_26") (pintype "bidirectional"))
    )
    (net (code "25") (name "/P26") (class "Default")
      (node (ref "JP3") (pin "14") (pinfunction "14_14") (pintype "passive"))
      (node (ref "U6") (pin "11") (pinfunction "LE_11") (pintype "passive"))
      (node (ref "U9") (pin "27") (pinfunction "P2.6/A14_27") (pintype "bidirectional"))
    )
    (net (code "26") (name "/P27") (class "Default")
      (node (ref "JP3") (pin "13") (pinfunction "13_13") (pintype "passive"))
      (node (ref "U7") (pin "11") (pinfunction "LE_11") (pintype "passive"))
      (node (ref "U9") (pin "28") (pinfunction "P2.7/A15_28") (pintype "bidirectional"))
    )
    (net (code "27") (name "/RST") (class "Default")
      (node (ref "C2") (pin "2") (pinfunction "2_2") (pintype "passive"))
      (node (ref "JP2") (pin "9") (pinfunction "9_9") (pintype "passive"))
      (node (ref "R64") (pin "2") (pinfunction "2_2") (pintype "passive"))
      (node (ref "U9") (pin "9") (pinfunction "RST_9") (pintype "passive"))
    )
    (net (code "28") (name "/RXD") (class "Default")
      (node (ref "JP1") (pin "2") (pinfunction "2_2") (pintype "passive"))
      (node (ref "JP2") (pin "10") (pinfunction "10_10") (pintype "passive"))
      (node (ref "U9") (pin "10") (pinfunction "RxD/P3.0_10") (pintype "bidirectional"))
    )
    (net (code "29") (name "/TXD") (class "Default")
      (node (ref "JP1") (pin "3") (pinfunction "3_3") (pintype "passive"))
      (node (ref "JP2") (pin "11") (pinfunction "11_11") (pintype "passive"))
      (node (ref "U9") (pin "11") (pinfunction "TxD/P3.1_11") (pintype "bidirectional"))
    )
    (net (code "30") (name "/XTAL1") (class "Default")
      (node (ref "C0") (pin "2") (pinfunction "2_2") (pintype "passive"))
      (node (ref "JP2") (pin "19") (pinfunction "19_19") (pintype "passive"))
      (node (ref "U9") (pin "19") (pinfunction "XTAL1_19") (pintype "passive"))
      (node (ref "Y0") (pin "2") (pinfunction "OSC2_2") (pintype "passive"))
    )
    (net (code "31") (name "/XTAL2") (class "Default")
      (node (ref "C1") (pin "2") (pinfunction "2_2") (pintype "passive"))
      (node (ref "JP2") (pin "18") (pinfunction "18_18") (pintype "passive"))
      (node (ref "U9") (pin "18") (pinfunction "XTAL2_18") (pintype "passive"))
      (node (ref "Y0") (pin "1") (pinfunction "OSC1_1") (pintype "passive"))
    )
    (net (code "32") (name "GND") (class "Default")
      (node (ref "C0") (pin "1") (pinfunction "1_1") (pintype "passive"))
      (node (ref "C1") (pin "1") (pinfunction "1_1") (pintype "passive"))
      (node (ref "C3") (pin "2") (pinfunction "2_2") (pintype "passive"))
      (node (ref "JP1") (pin "4") (pinfunction "4_4") (pintype "passive"))
      (node (ref "JP2") (pin "20") (pinfunction "20_20") (pintype "passive"))
      (node (ref "K3") (pin "B") (pinfunction "D_B") (pintype "passive"))
      (node (ref "K4") (pin "B") (pinfunction "D_B") (pintype "passive"))
      (node (ref "PORT0") (pin "5") (pinfunction "GND_5") (pintype "passive"))
      (node (ref "R64") (pin "1") (pinfunction "1_1") (pintype "passive"))
      (node (ref "R65") (pin "1") (pinfunction "1_1") (pintype "passive"))
      (node (ref "R66") (pin "2") (pinfunction "2_2") (pintype "passive"))
      (node (ref "U0") (pin "1") (pinfunction "~{OE}_1") (pintype "passive"))
      (node (ref "U0") (pin "10") (pinfunction "GND_10") (pintype "passive"))
      (node (ref "U1") (pin "1") (pinfunction "~{OE}_1") (pintype "passive"))
      (node (ref "U1") (pin "10") (pinfunction "GND_10") (pintype "passive"))
      (node (ref "U2") (pin "1") (pinfunction "~{OE}_1") (pintype "passive"))
      (node (ref "U2") (pin "10") (pinfunction "GND_10") (pintype "passive"))
      (node (ref "U3") (pin "1") (pinfunction "~{OE}_1") (pintype "passive"))
      (node (ref "U3") (pin "10") (pinfunction "GND_10") (pintype "passive"))
      (node (ref "U4") (pin "1") (pinfunction "~{OE}_1") (pintype "passive"))
      (node (ref "U4") (pin "10") (pinfunction "GND_10") (pintype "passive"))
      (node (ref "U5") (pin "1") (pinfunction "~{OE}_1") (pintype "passive"))
      (node (ref "U5") (pin "10") (pinfunction "GND_10") (pintype "passive"))
      (node (ref "U6") (pin "1") (pinfunction "~{OE}_1") (pintype "passive"))
      (node (ref "U6") (pin "10") (pinfunction "GND_10") (pintype "passive"))
      (node (ref "U7") (pin "1") (pinfunction "~{OE}_1") (pintype "passive"))
      (node (ref "U7") (pin "10") (pinfunction "GND_10") (pintype "passive"))
      (node (ref "U8") (pin "9") (pinfunction "GND_9") (pintype "passive"))
      (node (ref "U9") (pin "20") (pinfunction "GND_20") (pintype "passive"))
    )
    (net (code "33") (name "Net-(D0-A)") (class "Default")
      (node (ref "D0") (pin "1") (pinfunction "A_1") (pintype "passive"))
      (node (ref "K1") (pin "B") (pinfunction "D_B") (pintype "passive"))
    )
    (net (code "34") (name "Net-(D0-K)") (class "Default")
      (node (ref "D0") (pin "2") (pinfunction "K_2") (pintype "passive"))
      (node (ref "R66") (pin "1") (pinfunction "1_1") (pintype "passive"))
    )
    (net (code "35") (name "Net-(K0-11)") (class "Default")
      (node (ref "K0") (pin "D") (pinfunction "11_D") (pintype "passive"))
      (node (ref "R65") (pin "2") (pinfunction "2_2") (pintype "passive"))
    )
    (net (code "36") (name "Net-(K2-A0)") (class "Default")
      (node (ref "K2") (pin "1") (pinfunction "A0_1") (pintype "passive"))
      (node (ref "PORT0") (pin "1") (pinfunction "V++_1") (pintype "passive"))
    )
    (net (code "37") (name "Net-(P0-P)") (class "Default")
      (node (ref "P0") (pin "0") (pinfunction "P_0") (pintype "passive"))
      (node (ref "R0") (pin "2") (pinfunction "2_2") (pintype "passive"))
    )
    (net (code "38") (name "Net-(P1-P)") (class "Default")
      (node (ref "P1") (pin "0") (pinfunction "P_0") (pintype "passive"))
      (node (ref "R1") (pin "2") (pinfunction "2_2") (pintype "passive"))
    )
    (net (code "39") (name "Net-(P2-P)") (class "Default")
      (node (ref "P2") (pin "0") (pinfunction "P_0") (pintype "passive"))
      (node (ref "R2") (pin "2") (pinfunction "2_2") (pintype "passive"))
    )
    (net (code "40") (name "Net-(P3-P)") (class "Default")
      (node (ref "P3") (pin "0") (pinfunction "P_0") (pintype "passive"))
      (node (ref "R3") (pin "2") (pinfunction "2_2") (pintype "passive"))
    )
    (net (code "41") (name "Net-(P4-P)") (class "Default")
      (node (ref "P4") (pin "0") (pinfunction "P_0") (pintype "passive"))
      (node (ref "R4") (pin "2") (pinfunction "2_2") (pintype "passive"))
    )
    (net (code "42") (name "Net-(P5-P)") (class "Default")
      (node (ref "P5") (pin "0") (pinfunction "P_0") (pintype "passive"))
      (node (ref "R5") (pin "2") (pinfunction "2_2") (pintype "passive"))
    )
    (net (code "43") (name "Net-(P6-P)") (class "Default")
      (node (ref "P6") (pin "0") (pinfunction "P_0") (pintype "passive"))
      (node (ref "R6") (pin "2") (pinfunction "2_2") (pintype "passive"))
    )
    (net (code "44") (name "Net-(P7-P)") (class "Default")
      (node (ref "P7") (pin "0") (pinfunction "P_0") (pintype "passive"))
      (node (ref "R7") (pin "2") (pinfunction "2_2") (pintype "passive"))
    )
    (net (code "45") (name "Net-(P8-P)") (class "Default")
      (node (ref "P8") (pin "0") (pinfunction "P_0") (pintype "passive"))
      (node (ref "R8") (pin "2") (pinfunction "2_2") (pintype "passive"))
    )
    (net (code "46") (name "Net-(P9-P)") (class "Default")
      (node (ref "P9") (pin "0") (pinfunction "P_0") (pintype "passive"))
      (node (ref "R9") (pin "2") (pinfunction "2_2") (pintype "passive"))
    )
    (net (code "47") (name "Net-(P10-P)") (class "Default")
      (node (ref "P10") (pin "0") (pinfunction "P_0") (pintype "passive"))
      (node (ref "R10") (pin "2") (pinfunction "2_2") (pintype "passive"))
    )
    (net (code "48") (name "Net-(P11-P)") (class "Default")
      (node (ref "P11") (pin "0") (pinfunction "P_0") (pintype "passive"))
      (node (ref "R11") (pin "2") (pinfunction "2_2") (pintype "passive"))
    )
    (net (code "49") (name "Net-(P12-P)") (class "Default")
      (node (ref "P12") (pin "0") (pinfunction "P_0") (pintype "passive"))
      (node (ref "R12") (pin "2") (pinfunction "2_2") (pintype "passive"))
    )
    (net (code "50") (name "Net-(P13-P)") (class "Default")
      (node (ref "P13") (pin "0") (pinfunction "P_0") (pintype "passive"))
      (node (ref "R13") (pin "2") (pinfunction "2_2") (pintype "passive"))
    )
    (net (code "51") (name "Net-(P14-P)") (class "Default")
      (node (ref "P14") (pin "0") (pinfunction "P_0") (pintype "passive"))
      (node (ref "R14") (pin "2") (pinfunction "2_2") (pintype "passive"))
    )
    (net (code "52") (name "Net-(P15-P)") (class "Default")
      (node (ref "P15") (pin "0") (pinfunction "P_0") (pintype "passive"))
      (node (ref "R15") (pin "2") (pinfunction "2_2") (pintype "passive"))
    )
    (net (code "53") (name "Net-(P16-P)") (class "Default")
      (node (ref "P16") (pin "0") (pinfunction "P_0") (pintype "passive"))
      (node (ref "R16") (pin "2") (pinfunction "2_2") (pintype "passive"))
    )
    (net (code "54") (name "Net-(P17-P)") (class "Default")
      (node (ref "P17") (pin "0") (pinfunction "P_0") (pintype "passive"))
      (node (ref "R17") (pin "2") (pinfunction "2_2") (pintype "passive"))
    )
    (net (code "55") (name "Net-(P18-P)") (class "Default")
      (node (ref "P18") (pin "0") (pinfunction "P_0") (pintype "passive"))
      (node (ref "R18") (pin "2") (pinfunction "2_2") (pintype "passive"))
    )
    (net (code "56") (name "Net-(P19-P)") (class "Default")
      (node (ref "P19") (pin "0") (pinfunction "P_0") (pintype "passive"))
      (node (ref "R19") (pin "2") (pinfunction "2_2") (pintype "passive"))
    )
    (net (code "57") (name "Net-(P20-P)") (class "Default")
      (node (ref "P20") (pin "0") (pinfunction "P_0") (pintype "passive"))
      (node (ref "R20") (pin "2") (pinfunction "2_2") (pintype "passive"))
    )
    (net (code "58") (name "Net-(P21-P)") (class "Default")
      (node (ref "P21") (pin "0") (pinfunction "P_0") (pintype "passive"))
      (node (ref "R21") (pin "2") (pinfunction "2_2") (pintype "passive"))
    )
    (net (code "59") (name "Net-(P22-P)") (class "Default")
      (node (ref "P22") (pin "0") (pinfunction "P_0") (pintype "passive"))
      (node (ref "R22") (pin "2") (pinfunction "2_2") (pintype "passive"))
    )
    (net (code "60") (name "Net-(P23-P)") (class "Default")
      (node (ref "P23") (pin "0") (pinfunction "P_0") (pintype "passive"))
      (node (ref "R23") (pin "2") (pinfunction "2_2") (pintype "passive"))
    )
    (net (code "61") (name "Net-(P24-P)") (class "Default")
      (node (ref "P24") (pin "0") (pinfunction "P_0") (pintype "passive"))
      (node (ref "R24") (pin "2") (pinfunction "2_2") (pintype "passive"))
    )
    (net (code "62") (name "Net-(P25-P)") (class "Default")
      (node (ref "P25") (pin "0") (pinfunction "P_0") (pintype "passive"))
      (node (ref "R25") (pin "2") (pinfunction "2_2") (pintype "passive"))
    )
    (net (code "63") (name "Net-(P26-P)") (class "Default")
      (node (ref "P26") (pin "0") (pinfunction "P_0") (pintype "passive"))
      (node (ref "R26") (pin "2") (pinfunction "2_2") (pintype "passive"))
    )
    (net (code "64") (name "Net-(P27-P)") (class "Default")
      (node (ref "P27") (pin "0") (pinfunction "P_0") (pintype "passive"))
      (node (ref "R27") (pin "2") (pinfunction "2_2") (pintype "passive"))
    )
    (net (code "65") (name "Net-(P28-P)") (class "Default")
      (node (ref "P28") (pin "0") (pinfunction "P_0") (pintype "passive"))
      (node (ref "R28") (pin "2") (pinfunction "2_2") (pintype "passive"))
    )
    (net (code "66") (name "Net-(P29-P)") (class "Default")
      (node (ref "P29") (pin "0") (pinfunction "P_0") (pintype "passive"))
      (node (ref "R29") (pin "2") (pinfunction "2_2") (pintype "passive"))
    )
    (net (code "67") (name "Net-(P30-P)") (class "Default")
      (node (ref "P30") (pin "0") (pinfunction "P_0") (pintype "passive"))
      (node (ref "R30") (pin "2") (pinfunction "2_2") (pintype "passive"))
    )
    (net (code "68") (name "Net-(P31-P)") (class "Default")
      (node (ref "P31") (pin "0") (pinfunction "P_0") (pintype "passive"))
      (node (ref "R31") (pin "2") (pinfunction "2_2") (pintype "passive"))
    )
    (net (code "69") (name "Net-(P32-P)") (class "Default")
      (node (ref "P32") (pin "0") (pinfunction "P_0") (pintype "passive"))
      (node (ref "R32") (pin "2") (pinfunction "2_2") (pintype "passive"))
    )
    (net (code "70") (name "Net-(P33-P)") (class "Default")
      (node (ref "P33") (pin "0") (pinfunction "P_0") (pintype "passive"))
      (node (ref "R33") (pin "2") (pinfunction "2_2") (pintype "passive"))
    )
    (net (code "71") (name "Net-(P34-P)") (class "Default")
      (node (ref "P34") (pin "0") (pinfunction "P_0") (pintype "passive"))
      (node (ref "R34") (pin "2") (pinfunction "2_2") (pintype "passive"))
    )
    (net (code "72") (name "Net-(P35-P)") (class "Default")
      (node (ref "P35") (pin "0") (pinfunction "P_0") (pintype "passive"))
      (node (ref "R35") (pin "2") (pinfunction "2_2") (pintype "passive"))
    )
    (net (code "73") (name "Net-(P36-P)") (class "Default")
      (node (ref "P36") (pin "0") (pinfunction "P_0") (pintype "passive"))
      (node (ref "R36") (pin "2") (pinfunction "2_2") (pintype "passive"))
    )
    (net (code "74") (name "Net-(P37-P)") (class "Default")
      (node (ref "P37") (pin "0") (pinfunction "P_0") (pintype "passive"))
      (node (ref "R37") (pin "2") (pinfunction "2_2") (pintype "passive"))
    )
    (net (code "75") (name "Net-(P38-P)") (class "Default")
      (node (ref "P38") (pin "0") (pinfunction "P_0") (pintype "passive"))
      (node (ref "R38") (pin "2") (pinfunction "2_2") (pintype "passive"))
    )
    (net (code "76") (name "Net-(P39-P)") (class "Default")
      (node (ref "P39") (pin "0") (pinfunction "P_0") (pintype "passive"))
      (node (ref "R39") (pin "2") (pinfunction "2_2") (pintype "passive"))
    )
    (net (code "77") (name "Net-(P40-P)") (class "Default")
      (node (ref "P40") (pin "0") (pinfunction "P_0") (pintype "passive"))
      (node (ref "R40") (pin "2") (pinfunction "2_2") (pintype "passive"))
    )
    (net (code "78") (name "Net-(P41-P)") (class "Default")
      (node (ref "P41") (pin "0") (pinfunction "P_0") (pintype "passive"))
      (node (ref "R41") (pin "2") (pinfunction "2_2") (pintype "passive"))
    )
    (net (code "79") (name "Net-(P42-P)") (class "Default")
      (node (ref "P42") (pin "0") (pinfunction "P_0") (pintype "passive"))
      (node (ref "R42") (pin "2") (pinfunction "2_2") (pintype "passive"))
    )
    (net (code "80") (name "Net-(P43-P)") (class "Default")
      (node (ref "P43") (pin "0") (pinfunction "P_0") (pintype "passive"))
      (node (ref "R43") (pin "2") (pinfunction "2_2") (pintype "passive"))
    )
    (net (code "81") (name "Net-(P44-P)") (class "Default")
      (node (ref "P44") (pin "0") (pinfunction "P_0") (pintype "passive"))
      (node (ref "R44") (pin "2") (pinfunction "2_2") (pintype "passive"))
    )
    (net (code "82") (name "Net-(P45-P)") (class "Default")
      (node (ref "P45") (pin "0") (pinfunction "P_0") (pintype "passive"))
      (node (ref "R45") (pin "2") (pinfunction "2_2") (pintype "passive"))
    )
    (net (code "83") (name "Net-(P46-P)") (class "Default")
      (node (ref "P46") (pin "0") (pinfunction "P_0") (pintype "passive"))
      (node (ref "R46") (pin "2") (pinfunction "2_2") (pintype "passive"))
    )
    (net (code "84") (name "Net-(P47-P)") (class "Default")
      (node (ref "P47") (pin "0") (pinfunction "P_0") (pintype "passive"))
      (node (ref "R47") (pin "2") (pinfunction "2_2") (pintype "passive"))
    )
    (net (code "85") (name "Net-(P48-P)") (class "Default")
      (node (ref "P48") (pin "0") (pinfunction "P_0") (pintype "passive"))
      (node (ref "R48") (pin "2") (pinfunction "2_2") (pintype "passive"))
    )
    (net (code "86") (name "Net-(P49-P)") (class "Default")
      (node (ref "P49") (pin "0") (pinfunction "P_0") (pintype "passive"))
      (node (ref "R49") (pin "2") (pinfunction "2_2") (pintype "passive"))
    )
    (net (code "87") (name "Net-(P50-P)") (class "Default")
      (node (ref "P50") (pin "0") (pinfunction "P_0") (pintype "passive"))
      (node (ref "R50") (pin "2") (pinfunction "2_2") (pintype "passive"))
    )
    (net (code "88") (name "Net-(P51-P)") (class "Default")
      (node (ref "P51") (pin "0") (pinfunction "P_0") (pintype "passive"))
      (node (ref "R51") (pin "2") (pinfunction "2_2") (pintype "passive"))
    )
    (net (code "89") (name "Net-(P52-P)") (class "Default")
      (node (ref "P52") (pin "0") (pinfunction "P_0") (pintype "passive"))
      (node (ref "R52") (pin "2") (pinfunction "2_2") (pintype "passive"))
    )
    (net (code "90") (name "Net-(P53-P)") (class "Default")
      (node (ref "P53") (pin "0") (pinfunction "P_0") (pintype "passive"))
      (node (ref "R53") (pin "2") (pinfunction "2_2") (pintype "passive"))
    )
    (net (code "91") (name "Net-(P54-P)") (class "Default")
      (node (ref "P54") (pin "0") (pinfunction "P_0") (pintype "passive"))
      (node (ref "R54") (pin "2") (pinfunction "2_2") (pintype "passive"))
    )
    (net (code "92") (name "Net-(P55-P)") (class "Default")
      (node (ref "P55") (pin "0") (pinfunction "P_0") (pintype "passive"))
      (node (ref "R55") (pin "2") (pinfunction "2_2") (pintype "passive"))
    )
    (net (code "93") (name "Net-(P56-P)") (class "Default")
      (node (ref "P56") (pin "0") (pinfunction "P_0") (pintype "passive"))
      (node (ref "R56") (pin "2") (pinfunction "2_2") (pintype "passive"))
    )
    (net (code "94") (name "Net-(P57-P)") (class "Default")
      (node (ref "P57") (pin "0") (pinfunction "P_0") (pintype "passive"))
      (node (ref "R57") (pin "2") (pinfunction "2_2") (pintype "passive"))
    )
    (net (code "95") (name "Net-(P58-P)") (class "Default")
      (node (ref "P58") (pin "0") (pinfunction "P_0") (pintype "passive"))
      (node (ref "R58") (pin "2") (pinfunction "2_2") (pintype "passive"))
    )
    (net (code "96") (name "Net-(P59-P)") (class "Default")
      (node (ref "P59") (pin "0") (pinfunction "P_0") (pintype "passive"))
      (node (ref "R59") (pin "2") (pinfunction "2_2") (pintype "passive"))
    )
    (net (code "97") (name "Net-(P60-P)") (class "Default")
      (node (ref "P60") (pin "0") (pinfunction "P_0") (pintype "passive"))
      (node (ref "R60") (pin "2") (pinfunction "2_2") (pintype "passive"))
    )
    (net (code "98") (name "Net-(P61-P)") (class "Default")
      (node (ref "P61") (pin "0") (pinfunction "P_0") (pintype "passive"))
      (node (ref "R61") (pin "2") (pinfunction "2_2") (pintype "passive"))
    )
    (net (code "99") (name "Net-(P62-P)") (class "Default")
      (node (ref "P62") (pin "0") (pinfunction "P_0") (pintype "passive"))
      (node (ref "R62") (pin "2") (pinfunction "2_2") (pintype "passive"))
    )
    (net (code "100") (name "Net-(P63-P)") (class "Default")
      (node (ref "P63") (pin "0") (pinfunction "P_0") (pintype "passive"))
      (node (ref "R63") (pin "2") (pinfunction "2_2") (pintype "passive"))
    )
    (net (code "101") (name "Net-(U0-Q0)") (class "Default")
      (node (ref "R0") (pin "1") (pinfunction "1_1") (pintype "passive"))
      (node (ref "U0") (pin "19") (pinfunction "Q0_19") (pintype "output"))
    )
    (net (code "102") (name "Net-(U0-Q1)") (class "Default")
      (node (ref "R1") (pin "1") (pinfunction "1_1") (pintype "passive"))
      (node (ref "U0") (pin "18") (pinfunction "Q1_18") (pintype "output"))
    )
    (net (code "103") (name "Net-(U0-Q2)") (class "Default")
      (node (ref "R2") (pin "1") (pinfunction "1_1") (pintype "passive"))
      (node (ref "U0") (pin "17") (pinfunction "Q2_17") (pintype "output"))
    )
    (net (code "104") (name "Net-(U0-Q3)") (class "Default")
      (node (ref "R3") (pin "1") (pinfunction "1_1") (pintype "passive"))
      (node (ref "U0") (pin "16") (pinfunction "Q3_16") (pintype "output"))
    )
    (net (code "105") (name "Net-(U0-Q4)") (class "Default")
      (node (ref "R4") (pin "1") (pinfunction "1_1") (pintype "passive"))
      (node (ref "U0") (pin "15") (pinfunction "Q4_15") (pintype "output"))
    )
    (net (code "106") (name "Net-(U0-Q5)") (class "Default")
      (node (ref "R5") (pin "1") (pinfunction "1_1") (pintype "passive"))
      (node (ref "U0") (pin "14") (pinfunction "Q5_14") (pintype "output"))
    )
    (net (code "107") (name "Net-(U0-Q6)") (class "Default")
      (node (ref "R6") (pin "1") (pinfunction "1_1") (pintype "passive"))
      (node (ref "U0") (pin "13") (pinfunction "Q6_13") (pintype "output"))
    )
    (net (code "108") (name "Net-(U0-Q7)") (class "Default")
      (node (ref "R7") (pin "1") (pinfunction "1_1") (pintype "passive"))
      (node (ref "U0") (pin "12") (pinfunction "Q7_12") (pintype "output"))
    )
    (net (code "109") (name "Net-(U1-Q0)") (class "Default")
      (node (ref "R8") (pin "1") (pinfunction "1_1") (pintype "passive"))
      (node (ref "U1") (pin "19") (pinfunction "Q0_19") (pintype "output"))
    )
    (net (code "110") (name "Net-(U1-Q1)") (class "Default")
      (node (ref "R9") (pin "1") (pinfunction "1_1") (pintype "passive"))
      (node (ref "U1") (pin "18") (pinfunction "Q1_18") (pintype "output"))
    )
    (net (code "111") (name "Net-(U1-Q2)") (class "Default")
      (node (ref "R10") (pin "1") (pinfunction "1_1") (pintype "passive"))
      (node (ref "U1") (pin "17") (pinfunction "Q2_17") (pintype "output"))
    )
    (net (code "112") (name "Net-(U1-Q3)") (class "Default")
      (node (ref "R11") (pin "1") (pinfunction "1_1") (pintype "passive"))
      (node (ref "U1") (pin "16") (pinfunction "Q3_16") (pintype "output"))
    )
    (net (code "113") (name "Net-(U1-Q4)") (class "Default")
      (node (ref "R12") (pin "1") (pinfunction "1_1") (pintype "passive"))
      (node (ref "U1") (pin "15") (pinfunction "Q4_15") (pintype "output"))
    )
    (net (code "114") (name "Net-(U1-Q5)") (class "Default")
      (node (ref "R13") (pin "1") (pinfunction "1_1") (pintype "passive"))
      (node (ref "U1") (pin "14") (pinfunction "Q5_14") (pintype "output"))
    )
    (net (code "115") (name "Net-(U1-Q6)") (class "Default")
      (node (ref "R14") (pin "1") (pinfunction "1_1") (pintype "passive"))
      (node (ref "U1") (pin "13") (pinfunction "Q6_13") (pintype "output"))
    )
    (net (code "116") (name "Net-(U1-Q7)") (class "Default")
      (node (ref "R15") (pin "1") (pinfunction "1_1") (pintype "passive"))
      (node (ref "U1") (pin "12") (pinfunction "Q7_12") (pintype "output"))
    )
    (net (code "117") (name "Net-(U2-Q0)") (class "Default")
      (node (ref "R16") (pin "1") (pinfunction "1_1") (pintype "passive"))
      (node (ref "U2") (pin "19") (pinfunction "Q0_19") (pintype "output"))
    )
    (net (code "118") (name "Net-(U2-Q1)") (class "Default")
      (node (ref "R17") (pin "1") (pinfunction "1_1") (pintype "passive"))
      (node (ref "U2") (pin "18") (pinfunction "Q1_18") (pintype "output"))
    )
    (net (code "119") (name "Net-(U2-Q2)") (class "Default")
      (node (ref "R18") (pin "1") (pinfunction "1_1") (pintype "passive"))
      (node (ref "U2") (pin "17") (pinfunction "Q2_17") (pintype "output"))
    )
    (net (code "120") (name "Net-(U2-Q3)") (class "Default")
      (node (ref "R19") (pin "1") (pinfunction "1_1") (pintype "passive"))
      (node (ref "U2") (pin "16") (pinfunction "Q3_16") (pintype "output"))
    )
    (net (code "121") (name "Net-(U2-Q4)") (class "Default")
      (node (ref "R20") (pin "1") (pinfunction "1_1") (pintype "passive"))
      (node (ref "U2") (pin "15") (pinfunction "Q4_15") (pintype "output"))
    )
    (net (code "122") (name "Net-(U2-Q5)") (class "Default")
      (node (ref "R21") (pin "1") (pinfunction "1_1") (pintype "passive"))
      (node (ref "U2") (pin "14") (pinfunction "Q5_14") (pintype "output"))
    )
    (net (code "123") (name "Net-(U2-Q6)") (class "Default")
      (node (ref "R22") (pin "1") (pinfunction "1_1") (pintype "passive"))
      (node (ref "U2") (pin "13") (pinfunction "Q6_13") (pintype "output"))
    )
    (net (code "124") (name "Net-(U2-Q7)") (class "Default")
      (node (ref "R23") (pin "1") (pinfunction "1_1") (pintype "passive"))
      (node (ref "U2") (pin "12") (pinfunction "Q7_12") (pintype "output"))
    )
    (net (code "125") (name "Net-(U3-Q0)") (class "Default")
      (node (ref "R24") (pin "1") (pinfunction "1_1") (pintype "passive"))
      (node (ref "U3") (pin "19") (pinfunction "Q0_19") (pintype "output"))
    )
    (net (code "126") (name "Net-(U3-Q1)") (class "Default")
      (node (ref "R25") (pin "1") (pinfunction "1_1") (pintype "passive"))
      (node (ref "U3") (pin "18") (pinfunction "Q1_18") (pintype "output"))
    )
    (net (code "127") (name "Net-(U3-Q2)") (class "Default")
      (node (ref "R26") (pin "1") (pinfunction "1_1") (pintype "passive"))
      (node (ref "U3") (pin "17") (pinfunction "Q2_17") (pintype "output"))
    )
    (net (code "128") (name "Net-(U3-Q3)") (class "Default")
      (node (ref "R27") (pin "1") (pinfunction "1_1") (pintype "passive"))
      (node (ref "U3") (pin "16") (pinfunction "Q3_16") (pintype "output"))
    )
    (net (code "129") (name "Net-(U3-Q4)") (class "Default")
      (node (ref "R28") (pin "1") (pinfunction "1_1") (pintype "passive"))
      (node (ref "U3") (pin "15") (pinfunction "Q4_15") (pintype "output"))
    )
    (net (code "130") (name "Net-(U3-Q5)") (class "Default")
      (node (ref "R29") (pin "1") (pinfunction "1_1") (pintype "passive"))
      (node (ref "U3") (pin "14") (pinfunction "Q5_14") (pintype "output"))
    )
    (net (code "131") (name "Net-(U3-Q6)") (class "Default")
      (node (ref "R30") (pin "1") (pinfunction "1_1") (pintype "passive"))
      (node (ref "U3") (pin "13") (pinfunction "Q6_13") (pintype "output"))
    )
    (net (code "132") (name "Net-(U3-Q7)") (class "Default")
      (node (ref "R31") (pin "1") (pinfunction "1_1") (pintype "passive"))
      (node (ref "U3") (pin "12") (pinfunction "Q7_12") (pintype "output"))
    )
    (net (code "133") (name "Net-(U4-Q0)") (class "Default")
      (node (ref "R32") (pin "1") (pinfunction "1_1") (pintype "passive"))
      (node (ref "U4") (pin "19") (pinfunction "Q0_19") (pintype "output"))
    )
    (net (code "134") (name "Net-(U4-Q1)") (class "Default")
      (node (ref "R33") (pin "1") (pinfunction "1_1") (pintype "passive"))
      (node (ref "U4") (pin "18") (pinfunction "Q1_18") (pintype "output"))
    )
    (net (code "135") (name "Net-(U4-Q2)") (class "Default")
      (node (ref "R34") (pin "1") (pinfunction "1_1") (pintype "passive"))
      (node (ref "U4") (pin "17") (pinfunction "Q2_17") (pintype "output"))
    )
    (net (code "136") (name "Net-(U4-Q3)") (class "Default")
      (node (ref "R35") (pin "1") (pinfunction "1_1") (pintype "passive"))
      (node (ref "U4") (pin "16") (pinfunction "Q3_16") (pintype "output"))
    )
    (net (code "137") (name "Net-(U4-Q4)") (class "Default")
      (node (ref "R36") (pin "1") (pinfunction "1_1") (pintype "passive"))
      (node (ref "U4") (pin "15") (pinfunction "Q4_15") (pintype "output"))
    )
    (net (code "138") (name "Net-(U4-Q5)") (class "Default")
      (node (ref "R37") (pin "1") (pinfunction "1_1") (pintype "passive"))
      (node (ref "U4") (pin "14") (pinfunction "Q5_14") (pintype "output"))
    )
    (net (code "139") (name "Net-(U4-Q6)") (class "Default")
      (node (ref "R38") (pin "1") (pinfunction "1_1") (pintype "passive"))
      (node (ref "U4") (pin "13") (pinfunction "Q6_13") (pintype "output"))
    )
    (net (code "140") (name "Net-(U4-Q7)") (class "Default")
      (node (ref "R39") (pin "1") (pinfunction "1_1") (pintype "passive"))
      (node (ref "U4") (pin "12") (pinfunction "Q7_12") (pintype "output"))
    )
    (net (code "141") (name "Net-(U5-Q0)") (class "Default")
      (node (ref "R40") (pin "1") (pinfunction "1_1") (pintype "passive"))
      (node (ref "U5") (pin "19") (pinfunction "Q0_19") (pintype "output"))
    )
    (net (code "142") (name "Net-(U5-Q1)") (class "Default")
      (node (ref "R41") (pin "1") (pinfunction "1_1") (pintype "passive"))
      (node (ref "U5") (pin "18") (pinfunction "Q1_18") (pintype "output"))
    )
    (net (code "143") (name "Net-(U5-Q2)") (class "Default")
      (node (ref "R42") (pin "1") (pinfunction "1_1") (pintype "passive"))
      (node (ref "U5") (pin "17") (pinfunction "Q2_17") (pintype "output"))
    )
    (net (code "144") (name "Net-(U5-Q3)") (class "Default")
      (node (ref "R43") (pin "1") (pinfunction "1_1") (pintype "passive"))
      (node (ref "U5") (pin "16") (pinfunction "Q3_16") (pintype "output"))
    )
    (net (code "145") (name "Net-(U5-Q4)") (class "Default")
      (node (ref "R44") (pin "1") (pinfunction "1_1") (pintype "passive"))
      (node (ref "U5") (pin "15") (pinfunction "Q4_15") (pintype "output"))
    )
    (net (code "146") (name "Net-(U5-Q5)") (class "Default")
      (node (ref "R45") (pin "1") (pinfunction "1_1") (pintype "passive"))
      (node (ref "U5") (pin "14") (pinfunction "Q5_14") (pintype "output"))
    )
    (net (code "147") (name "Net-(U5-Q6)") (class "Default")
      (node (ref "R46") (pin "1") (pinfunction "1_1") (pintype "passive"))
      (node (ref "U5") (pin "13") (pinfunction "Q6_13") (pintype "output"))
    )
    (net (code "148") (name "Net-(U5-Q7)") (class "Default")
      (node (ref "R47") (pin "1") (pinfunction "1_1") (pintype "passive"))
      (node (ref "U5") (pin "12") (pinfunction "Q7_12") (pintype "output"))
    )
    (net (code "149") (name "Net-(U6-Q0)") (class "Default")
      (node (ref "R48") (pin "1") (pinfunction "1_1") (pintype "passive"))
      (node (ref "U6") (pin "19") (pinfunction "Q0_19") (pintype "output"))
    )
    (net (code "150") (name "Net-(U6-Q1)") (class "Default")
      (node (ref "R49") (pin "1") (pinfunction "1_1") (pintype "passive"))
      (node (ref "U6") (pin "18") (pinfunction "Q1_18") (pintype "output"))
    )
    (net (code "151") (name "Net-(U6-Q2)") (class "Default")
      (node (ref "R50") (pin "1") (pinfunction "1_1") (pintype "passive"))
      (node (ref "U6") (pin "17") (pinfunction "Q2_17") (pintype "output"))
    )
    (net (code "152") (name "Net-(U6-Q3)") (class "Default")
      (node (ref "R51") (pin "1") (pinfunction "1_1") (pintype "passive"))
      (node (ref "U6") (pin "16") (pinfunction "Q3_16") (pintype "output"))
    )
    (net (code "153") (name "Net-(U6-Q4)") (class "Default")
      (node (ref "R52") (pin "1") (pinfunction "1_1") (pintype "passive"))
      (node (ref "U6") (pin "15") (pinfunction "Q4_15") (pintype "output"))
    )
    (net (code "154") (name "Net-(U6-Q5)") (class "Default")
      (node (ref "R53") (pin "1") (pinfunction "1_1") (pintype "passive"))
      (node (ref "U6") (pin "14") (pinfunction "Q5_14") (pintype "output"))
    )
    (net (code "155") (name "Net-(U6-Q6)") (class "Default")
      (node (ref "R54") (pin "1") (pinfunction "1_1") (pintype "passive"))
      (node (ref "U6") (pin "13") (pinfunction "Q6_13") (pintype "output"))
    )
    (net (code "156") (name "Net-(U6-Q7)") (class "Default")
      (node (ref "R55") (pin "1") (pinfunction "1_1") (pintype "passive"))
      (node (ref "U6") (pin "12") (pinfunction "Q7_12") (pintype "output"))
    )
    (net (code "157") (name "Net-(U7-Q0)") (class "Default")
      (node (ref "R56") (pin "1") (pinfunction "1_1") (pintype "passive"))
      (node (ref "U7") (pin "19") (pinfunction "Q0_19") (pintype "output"))
    )
    (net (code "158") (name "Net-(U7-Q1)") (class "Default")
      (node (ref "R57") (pin "1") (pinfunction "1_1") (pintype "passive"))
      (node (ref "U7") (pin "18") (pinfunction "Q1_18") (pintype "output"))
    )
    (net (code "159") (name "Net-(U7-Q2)") (class "Default")
      (node (ref "R58") (pin "1") (pinfunction "1_1") (pintype "passive"))
      (node (ref "U7") (pin "17") (pinfunction "Q2_17") (pintype "output"))
    )
    (net (code "160") (name "Net-(U7-Q3)") (class "Default")
      (node (ref "R59") (pin "1") (pinfunction "1_1") (pintype "passive"))
      (node (ref "U7") (pin "16") (pinfunction "Q3_16") (pintype "output"))
    )
    (net (code "161") (name "Net-(U7-Q4)") (class "Default")
      (node (ref "R60") (pin "1") (pinfunction "1_1") (pintype "passive"))
      (node (ref "U7") (pin "15") (pinfunction "Q4_15") (pintype "output"))
    )
    (net (code "162") (name "Net-(U7-Q5)") (class "Default")
      (node (ref "R61") (pin "1") (pinfunction "1_1") (pintype "passive"))
      (node (ref "U7") (pin "14") (pinfunction "Q5_14") (pintype "output"))
    )
    (net (code "163") (name "Net-(U7-Q6)") (class "Default")
      (node (ref "R62") (pin "1") (pinfunction "1_1") (pintype "passive"))
      (node (ref "U7") (pin "13") (pinfunction "Q6_13") (pintype "output"))
    )
    (net (code "164") (name "Net-(U7-Q7)") (class "Default")
      (node (ref "R63") (pin "1") (pinfunction "1_1") (pintype "passive"))
      (node (ref "U7") (pin "12") (pinfunction "Q7_12") (pintype "output"))
    )
    (net (code "165") (name "Net-(U8-OUT1)") (class "Default")
      (node (ref "JP0") (pin "1") (pinfunction "1_1") (pintype "passive"))
      (node (ref "RP1") (pin "1") (pinfunction "1_1") (pintype "passive"))
      (node (ref "U8") (pin "18") (pinfunction "OUT1_18") (pintype "output"))
    )
    (net (code "166") (name "Net-(U8-OUT2)") (class "Default")
      (node (ref "JP0") (pin "2") (pinfunction "2_2") (pintype "passive"))
      (node (ref "RP1") (pin "2") (pinfunction "2_2") (pintype "passive"))
      (node (ref "U8") (pin "17") (pinfunction "OUT2_17") (pintype "output"))
    )
    (net (code "167") (name "Net-(U8-OUT3)") (class "Default")
      (node (ref "JP0") (pin "3") (pinfunction "3_3") (pintype "passive"))
      (node (ref "RP1") (pin "3") (pinfunction "3_3") (pintype "passive"))
      (node (ref "U8") (pin "16") (pinfunction "OUT3_16") (pintype "output"))
    )
    (net (code "168") (name "Net-(U8-OUT4)") (class "Default")
      (node (ref "JP0") (pin "4") (pinfunction "4_4") (pintype "passive"))
      (node (ref "RP1") (pin "4") (pinfunction "4_4") (pintype "passive"))
      (node (ref "U8") (pin "15") (pinfunction "OUT4_15") (pintype "output"))
    )
    (net (code "169") (name "Net-(U8-OUT5)") (class "Default")
      (node (ref "JP0") (pin "5") (pinfunction "5_5") (pintype "passive"))
      (node (ref "RP1") (pin "5") (pinfunction "5_5") (pintype "passive"))
      (node (ref "U8") (pin "14") (pinfunction "OUT5_14") (pintype "output"))
    )
    (net (code "170") (name "Net-(U8-OUT6)") (class "Default")
      (node (ref "JP0") (pin "6") (pinfunction "6_6") (pintype "passive"))
      (node (ref "RP1") (pin "6") (pinfunction "6_6") (pintype "passive"))
      (node (ref "U8") (pin "13") (pinfunction "OUT6_13") (pintype "output"))
    )
    (net (code "171") (name "Net-(U8-OUT7)") (class "Default")
      (node (ref "JP0") (pin "7") (pinfunction "7_7") (pintype "passive"))
      (node (ref "RP1") (pin "7") (pinfunction "7_7") (pintype "passive"))
      (node (ref "U8") (pin "12") (pinfunction "OUT7_12") (pintype "output"))
    )
    (net (code "172") (name "Net-(U8-OUT8)") (class "Default")
      (node (ref "JP0") (pin "8") (pinfunction "8_8") (pintype "passive"))
      (node (ref "RP1") (pin "8") (pinfunction "8_8") (pintype "passive"))
      (node (ref "U8") (pin "11") (pinfunction "OUT8_11") (pintype "output"))
    )
    (net (code "173") (name "Net-(U9-ALE{slash}P4.5)") (class "Default")
      (node (ref "JP3") (pin "11") (pinfunction "11_11") (pintype "passive"))
      (node (ref "U9") (pin "30") (pinfunction "ALE/P4.5_30") (pintype "passive"))
    )
    (net (code "174") (name "Net-(U9-T0{slash}P3.4)") (class "Default")
      (node (ref "JP2") (pin "14") (pinfunction "14_14") (pintype "passive"))
      (node (ref "U9") (pin "14") (pinfunction "T0/P3.4_14") (pintype "bidirectional"))
    )
    (net (code "175") (name "Net-(U9-T1{slash}P3.5)") (class "Default")
      (node (ref "JP2") (pin "15") (pinfunction "15_15") (pintype "passive"))
      (node (ref "U9") (pin "15") (pinfunction "T1/P3.5_15") (pintype "bidirectional"))
    )
    (net (code "176") (name "Net-(U9-~{EA}{slash}P4.6)") (class "Default")
      (node (ref "JP3") (pin "10") (pinfunction "10_10") (pintype "passive"))
      (node (ref "U9") (pin "31") (pinfunction "~{EA}/P4.6_31") (pintype "passive"))
    )
    (net (code "177") (name "Net-(U9-~{PSEN}{slash}P4.4)") (class "Default")
      (node (ref "JP3") (pin "12") (pinfunction "12_12") (pintype "passive"))
      (node (ref "U9") (pin "29") (pinfunction "~{PSEN}/P4.4_29") (pintype "passive"))
    )
    (net (code "178") (name "Net-(U9-~{RD}{slash}P3.7)") (class "Default")
      (node (ref "JP2") (pin "17") (pinfunction "17_17") (pintype "passive"))
      (node (ref "U9") (pin "17") (pinfunction "~{RD}/P3.7_17") (pintype "bidirectional"))
    )
    (net (code "179") (name "Net-(U9-~{WR}{slash}P3.6)") (class "Default")
      (node (ref "JP2") (pin "16") (pinfunction "16_16") (pintype "passive"))
      (node (ref "U9") (pin "16") (pinfunction "~{WR}/P3.6_16") (pintype "bidirectional"))
    )
    (net (code "180") (name "VCC") (class "Default")
      (node (ref "C2") (pin "1") (pinfunction "1_1") (pintype "passive"))
      (node (ref "C3") (pin "1") (pinfunction "1_1") (pintype "passive"))
      (node (ref "JP1") (pin "1") (pinfunction "1_1") (pintype "passive"))
      (node (ref "JP3") (pin "1") (pinfunction "1_1") (pintype "passive"))
      (node (ref "K0") (pin "C") (pinfunction "12_C") (pintype "passive"))
      (node (ref "K1") (pin "C") (pinfunction "12_C") (pintype "passive"))
      (node (ref "K2") (pin "2") (pinfunction "COM0_2") (pintype "passive"))
      (node (ref "RP0") (pin "0") (pinfunction "C_0") (pintype "passive"))
      (node (ref "RP1") (pin "0") (pinfunction "C_0") (pintype "passive"))
      (node (ref "U0") (pin "20") (pinfunction "VCC_20") (pintype "power_in"))
      (node (ref "U1") (pin "20") (pinfunction "VCC_20") (pintype "power_in"))
      (node (ref "U2") (pin "20") (pinfunction "VCC_20") (pintype "power_in"))
      (node (ref "U3") (pin "20") (pinfunction "VCC_20") (pintype "power_in"))
      (node (ref "U4") (pin "20") (pinfunction "VCC_20") (pintype "power_in"))
      (node (ref "U5") (pin "20") (pinfunction "VCC_20") (pintype "power_in"))
      (node (ref "U6") (pin "20") (pinfunction "VCC_20") (pintype "power_in"))
      (node (ref "U7") (pin "20") (pinfunction "VCC_20") (pintype "power_in"))
      (node (ref "U8") (pin "10") (pinfunction "COM_10") (pintype "passive"))
      (node (ref "U9") (pin "40") (pinfunction "VCC_40") (pintype "power_in"))
    )
    (net (code "181") (name "unconnected-(K0-D-PadA)") (class "Default")
      (node (ref "K0") (pin "A") (pinfunction "D_A") (pintype "passive"))
    )
    (net (code "182") (name "unconnected-(K0-D-PadB)") (class "Default")
      (node (ref "K0") (pin "B") (pinfunction "D_B") (pintype "passive"))
    )
    (net (code "183") (name "unconnected-(K1-11-PadD)") (class "Default")
      (node (ref "K1") (pin "D") (pinfunction "11_D") (pintype "passive"))
    )
    (net (code "184") (name "unconnected-(K1-D-PadA)") (class "Default")
      (node (ref "K1") (pin "A") (pinfunction "D_A") (pintype "passive"))
    )
    (net (code "185") (name "unconnected-(K2-A1-Pad6)") (class "Default")
      (node (ref "K2") (pin "6") (pinfunction "A1_6") (pintype "passive"))
    )
    (net (code "186") (name "unconnected-(K2-B0-Pad3)") (class "Default")
      (node (ref "K2") (pin "3") (pinfunction "B0_3") (pintype "passive"))
    )
    (net (code "187") (name "unconnected-(K2-B1-Pad4)") (class "Default")
      (node (ref "K2") (pin "4") (pinfunction "B1_4") (pintype "passive"))
    )
    (net (code "188") (name "unconnected-(K2-COM1-Pad5)") (class "Default")
      (node (ref "K2") (pin "5") (pinfunction "COM1_5") (pintype "passive"))
    )
    (net (code "189") (name "unconnected-(K3-11-PadD)") (class "Default")
      (node (ref "K3") (pin "D") (pinfunction "11_D") (pintype "passive"))
    )
    (net (code "190") (name "unconnected-(K3-D-PadA)") (class "Default")
      (node (ref "K3") (pin "A") (pinfunction "D_A") (pintype "passive"))
    )
    (net (code "191") (name "unconnected-(K4-11-PadD)") (class "Default")
      (node (ref "K4") (pin "D") (pinfunction "11_D") (pintype "passive"))
    )
    (net (code "192") (name "unconnected-(K4-D-PadA)") (class "Default")
      (node (ref "K4") (pin "A") (pinfunction "D_A") (pintype "passive"))
    )
    (net (code "193") (name "unconnected-(PORT0-D+-Pad3)") (class "Default")
      (node (ref "PORT0") (pin "3") (pinfunction "D+_3") (pintype "passive"))
    )
    (net (code "194") (name "unconnected-(PORT0-D--Pad2)") (class "Default")
      (node (ref "PORT0") (pin "2") (pinfunction "D-_2") (pintype "passive"))
    )
    (net (code "195") (name "unconnected-(PORT0-ID-Pad4)") (class "Default")
      (node (ref "PORT0") (pin "4") (pinfunction "ID_4") (pintype "passive"))
    )
  )
)
